# blinky-leds.net
KiCad netlist of a schematic drawn in EAGLE
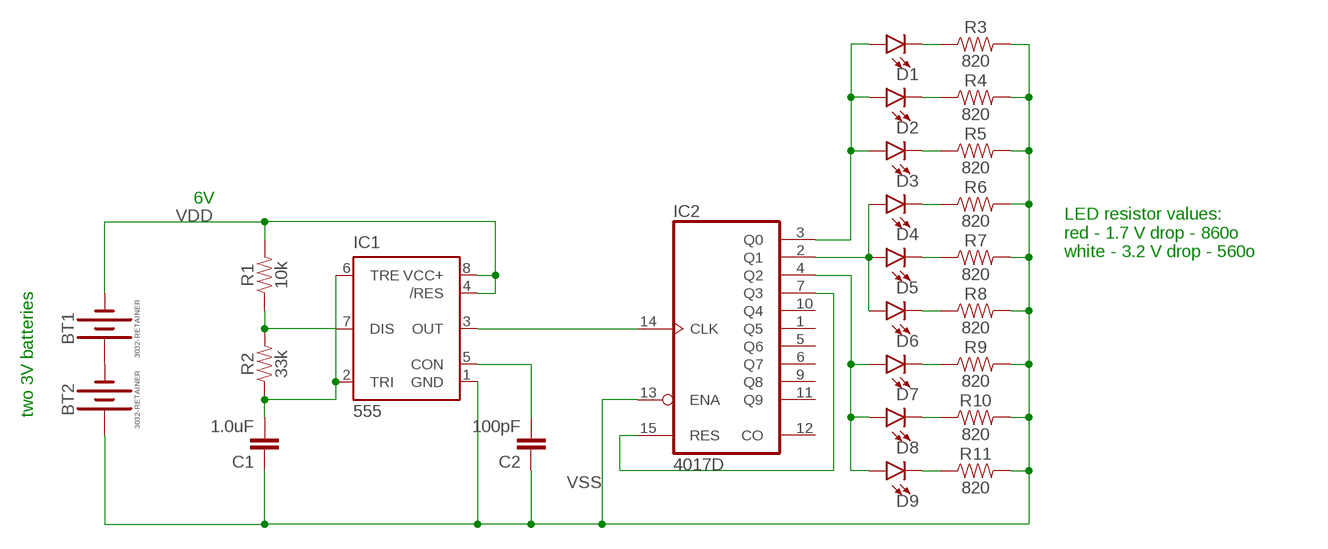
[diagram p0: schematic, sheet 1]

(export (version "E")
  (design (tool "Eeschema 10.0.6"))
  (components
    (comp (ref "BT1")
      (value "3032-RETAINER")
      (footprint "eagle-import:KEYSTONE-3034")
      (libsource (lib "eagle-import") (part "3032-RETAINER"))
    )
    (comp (ref "BT2")
      (value "3032-RETAINER")
      (footprint "eagle-import:KEYSTONE-3034")
      (libsource (lib "eagle-import") (part "3032-RETAINER"))
    )
    (comp (ref "C1")
      (value "1.0uF")
      (footprint "eagle-import:0603")
      (libsource (lib "eagle-import") (part "1.0UF-0603-16V-10%"))
    )
    (comp (ref "C2")
      (value "100pF")
      (footprint "eagle-import:0603")
      (libsource (lib "eagle-import") (part "100PF-0603-50V-5%"))
    )
    (comp (ref "D1")
      (value "LED0603")
      (footprint "eagle-import:LED-0603")
      (libsource (lib "eagle-import") (part "LED0603"))
    )
    (comp (ref "D2")
      (value "LED0603")
      (footprint "eagle-import:LED-0603")
      (libsource (lib "eagle-import") (part "LED0603"))
    )
    (comp (ref "D3")
      (value "LED0603")
      (footprint "eagle-import:LED-0603")
      (libsource (lib "eagle-import") (part "LED0603"))
    )
    (comp (ref "D4")
      (value "LED0603")
      (footprint "eagle-import:LED-0603")
      (libsource (lib "eagle-import") (part "LED0603"))
    )
    (comp (ref "D5")
      (value "LED0603")
      (footprint "eagle-import:LED-0603")
      (libsource (lib "eagle-import") (part "LED0603"))
    )
    (comp (ref "D6")
      (value "LED0603")
      (footprint "eagle-import:LED-0603")
      (libsource (lib "eagle-import") (part "LED0603"))
    )
    (comp (ref "D7")
      (value "LED0603")
      (footprint "eagle-import:LED-0603")
      (libsource (lib "eagle-import") (part "LED0603"))
    )
    (comp (ref "D8")
      (value "LED0603")
      (footprint "eagle-import:LED-0603")
      (libsource (lib "eagle-import") (part "LED0603"))
    )
    (comp (ref "D9")
      (value "LED0603")
      (footprint "eagle-import:LED-0603")
      (libsource (lib "eagle-import") (part "LED0603"))
    )
    (comp (ref "IC1")
      (value "555")
      (footprint "eagle-import:SO08")
      (libsource (lib "eagle-import") (part "555D"))
    )
    (comp (ref "IC2")
      (value "4017D")
      (footprint "eagle-import:SO16")
      (libsource (lib "eagle-import") (part "4017D"))
    )
    (comp (ref "R1")
      (value "10k")
      (footprint "eagle-import:0603")
      (libsource (lib "eagle-import") (part "10KOHM-0603-1/10W-1%"))
    )
    (comp (ref "R2")
      (value "33k")
      (footprint "eagle-import:0603")
      (libsource (lib "eagle-import") (part "33KOHM-0603-1/10W-1%"))
    )
    (comp (ref "R3")
      (value "820")
      (footprint "eagle-import:0603")
      (libsource (lib "eagle-import") (part "RESISTOR0603"))
    )
    (comp (ref "R4")
      (value "820")
      (footprint "eagle-import:0603")
      (libsource (lib "eagle-import") (part "RESISTOR0603"))
    )
    (comp (ref "R5")
      (value "820")
      (footprint "eagle-import:0603")
      (libsource (lib "eagle-import") (part "RESISTOR0603"))
    )
    (comp (ref "R6")
      (value "820")
      (footprint "eagle-import:0603")
      (libsource (lib "eagle-import") (part "RESISTOR0603"))
    )
    (comp (ref "R7")
      (value "820")
      (footprint "eagle-import:0603")
      (libsource (lib "eagle-import") (part "RESISTOR0603"))
    )
    (comp (ref "R8")
      (value "820")
      (footprint "eagle-import:0603")
      (libsource (lib "eagle-import") (part "RESISTOR0603"))
    )
    (comp (ref "R9")
      (value "820")
      (footprint "eagle-import:0603")
      (libsource (lib "eagle-import") (part "RESISTOR0603"))
    )
    (comp (ref "R10")
      (value "820")
      (footprint "eagle-import:0603")
      (libsource (lib "eagle-import") (part "RESISTOR0603"))
    )
    (comp (ref "R11")
      (value "820")
      (footprint "eagle-import:0603")
      (libsource (lib "eagle-import") (part "RESISTOR0603"))
    )
  )
  (nets
    (net (code "1") (name "/VDD") (class "Default")
      (node (ref "BT1") (pin "P$2") (pinfunction "-_P$2") (pintype "power_in"))
      (node (ref "BT1") (pin "P$3") (pinfunction "-_P$3") (pintype "power_in"))
      (node (ref "IC1") (pin "4") (pinfunction "/RES_4") (pintype "input"))
      (node (ref "IC1") (pin "8") (pinfunction "VCC+_8") (pintype "power_in"))
      (node (ref "R1") (pin "2") (pinfunction "2_2") (pintype "passive"))
    )
    (net (code "2") (name "/VSS") (class "Default")
      (node (ref "BT2") (pin "P$1") (pinfunction "+_P$1") (pintype "power_in"))
      (node (ref "C1") (pin "1") (pinfunction "1_1") (pintype "passive"))
      (node (ref "C2") (pin "1") (pinfunction "1_1") (pintype "passive"))
      (node (ref "IC1") (pin "1") (pinfunction "GND_1") (pintype "power_in"))
      (node (ref "IC2") (pin "13") (pinfunction "ENA_13") (pintype "input"))
      (node (ref "R10") (pin "2") (pinfunction "2_2") (pintype "passive"))
      (node (ref "R11") (pin "2") (pinfunction "2_2") (pintype "passive"))
      (node (ref "R3") (pin "2") (pinfunction "2_2") (pintype "passive"))
      (node (ref "R4") (pin "2") (pinfunction "2_2") (pintype "passive"))
      (node (ref "R5") (pin "2") (pinfunction "2_2") (pintype "passive"))
      (node (ref "R6") (pin "2") (pinfunction "2_2") (pintype "passive"))
      (node (ref "R7") (pin "2") (pinfunction "2_2") (pintype "passive"))
      (node (ref "R8") (pin "2") (pinfunction "2_2") (pintype "passive"))
      (node (ref "R9") (pin "2") (pinfunction "2_2") (pintype "passive"))
    )
    (net (code "3") (name "Net-(BT1-+)") (class "Default")
      (node (ref "BT1") (pin "P$1") (pinfunction "+_P$1") (pintype "power_in"))
      (node (ref "BT2") (pin "P$2") (pinfunction "-_P$2") (pintype "power_in"))
      (node (ref "BT2") (pin "P$3") (pinfunction "-_P$3") (pintype "power_in"))
    )
    (net (code "4") (name "Net-(D1-PadC)") (class "Default")
      (node (ref "D1") (pin "C") (pinfunction "C_C") (pintype "passive"))
      (node (ref "R3") (pin "1") (pinfunction "1_1") (pintype "passive"))
    )
    (net (code "5") (name "Net-(D2-PadC)") (class "Default")
      (node (ref "D2") (pin "C") (pinfunction "C_C") (pintype "passive"))
      (node (ref "R4") (pin "1") (pinfunction "1_1") (pintype "passive"))
    )
    (net (code "6") (name "Net-(D3-PadC)") (class "Default")
      (node (ref "D3") (pin "C") (pinfunction "C_C") (pintype "passive"))
      (node (ref "R5") (pin "1") (pinfunction "1_1") (pintype "passive"))
    )
    (net (code "7") (name "Net-(D4-PadC)") (class "Default")
      (node (ref "D4") (pin "C") (pinfunction "C_C") (pintype "passive"))
      (node (ref "R6") (pin "1") (pinfunction "1_1") (pintype "passive"))
    )
    (net (code "8") (name "Net-(D5-PadC)") (class "Default")
      (node (ref "D5") (pin "C") (pinfunction "C_C") (pintype "passive"))
      (node (ref "R7") (pin "1") (pinfunction "1_1") (pintype "passive"))
    )
    (net (code "9") (name "Net-(D6-PadC)") (class "Default")
      (node (ref "D6") (pin "C") (pinfunction "C_C") (pintype "passive"))
      (node (ref "R8") (pin "1") (pinfunction "1_1") (pintype "passive"))
    )
    (net (code "10") (name "Net-(D7-PadC)") (class "Default")
      (node (ref "D7") (pin "C") (pinfunction "C_C") (pintype "passive"))
      (node (ref "R9") (pin "1") (pinfunction "1_1") (pintype "passive"))
    )
    (net (code "11") (name "Net-(D8-PadC)") (class "Default")
      (node (ref "D8") (pin "C") (pinfunction "C_C") (pintype "passive"))
      (node (ref "R10") (pin "1") (pinfunction "1_1") (pintype "passive"))
    )
    (net (code "12") (name "Net-(D9-PadC)") (class "Default")
      (node (ref "D9") (pin "C") (pinfunction "C_C") (pintype "passive"))
      (node (ref "R11") (pin "1") (pinfunction "1_1") (pintype "passive"))
    )
    (net (code "13") (name "Net-(IC1-CON)") (class "Default")
      (node (ref "C2") (pin "2") (pinfunction "2_2") (pintype "passive"))
      (node (ref "IC1") (pin "5") (pinfunction "CON_5") (pintype "input"))
    )
    (net (code "14") (name "Net-(IC1-DIS)") (class "Default")
      (node (ref "IC1") (pin "7") (pinfunction "DIS_7") (pintype "input"))
      (node (ref "R1") (pin "1") (pinfunction "1_1") (pintype "passive"))
      (node (ref "R2") (pin "2") (pinfunction "2_2") (pintype "passive"))
    )
    (net (code "15") (name "Net-(IC1-OUT)") (class "Default")
      (node (ref "IC1") (pin "3") (pinfunction "OUT_3") (pintype "output"))
      (node (ref "IC2") (pin "14") (pinfunction "CLK_14") (pintype "input"))
    )
    (net (code "16") (name "Net-(IC1-TRE)") (class "Default")
      (node (ref "C1") (pin "2") (pinfunction "2_2") (pintype "passive"))
      (node (ref "IC1") (pin "2") (pinfunction "TRI_2") (pintype "input"))
      (node (ref "IC1") (pin "6") (pinfunction "TRE_6") (pintype "input"))
      (node (ref "R2") (pin "1") (pinfunction "1_1") (pintype "passive"))
    )
    (net (code "17") (name "Net-(IC2A-Q0)") (class "Default")
      (node (ref "D1") (pin "A") (pinfunction "A_A") (pintype "passive"))
      (node (ref "D2") (pin "A") (pinfunction "A_A") (pintype "passive"))
      (node (ref "D3") (pin "A") (pinfunction "A_A") (pintype "passive"))
      (node (ref "IC2") (pin "3") (pinfunction "Q0_3") (pintype "output"))
    )
    (net (code "18") (name "Net-(IC2A-Q1)") (class "Default")
      (node (ref "D4") (pin "A") (pinfunction "A_A") (pintype "passive"))
      (node (ref "D5") (pin "A") (pinfunction "A_A") (pintype "passive"))
      (node (ref "D6") (pin "A") (pinfunction "A_A") (pintype "passive"))
      (node (ref "IC2") (pin "2") (pinfunction "Q1_2") (pintype "output"))
    )
    (net (code "19") (name "Net-(IC2A-Q2)") (class "Default")
      (node (ref "D7") (pin "A") (pinfunction "A_A") (pintype "passive"))
      (node (ref "D8") (pin "A") (pinfunction "A_A") (pintype "passive"))
      (node (ref "D9") (pin "A") (pinfunction "A_A") (pintype "passive"))
      (node (ref "IC2") (pin "4") (pinfunction "Q2_4") (pintype "output"))
    )
    (net (code "20") (name "Net-(IC2A-Q3)") (class "Default")
      (node (ref "IC2") (pin "15") (pinfunction "RES_15") (pintype "input"))
      (node (ref "IC2") (pin "7") (pinfunction "Q3_7") (pintype "output"))
    )
    (net (code "21") (name "unconnected-(IC2A-CO-Pad12)") (class "Default")
      (node (ref "IC2") (pin "12") (pinfunction "CO_12") (pintype "output"))
    )
    (net (code "22") (name "unconnected-(IC2A-Q4-Pad10)") (class "Default")
      (node (ref "IC2") (pin "10") (pinfunction "Q4_10") (pintype "output"))
    )
    (net (code "23") (name "unconnected-(IC2A-Q5-Pad1)") (class "Default")
      (node (ref "IC2") (pin "1") (pinfunction "Q5_1") (pintype "output"))
    )
    (net (code "24") (name "unconnected-(IC2A-Q6-Pad5)") (class "Default")
      (node (ref "IC2") (pin "5") (pinfunction "Q6_5") (pintype "output"))
    )
    (net (code "25") (name "unconnected-(IC2A-Q7-Pad6)") (class "Default")
      (node (ref "IC2") (pin "6") (pinfunction "Q7_6") (pintype "output"))
    )
    (net (code "26") (name "unconnected-(IC2A-Q8-Pad9)") (class "Default")
      (node (ref "IC2") (pin "9") (pinfunction "Q8_9") (pintype "output"))
    )
    (net (code "27") (name "unconnected-(IC2A-Q9-Pad11)") (class "Default")
      (node (ref "IC2") (pin "11") (pinfunction "Q9_11") (pintype "output"))
    )
  )
)
